# design.net
KiCad netlist of a schematic drawn in EAGLE
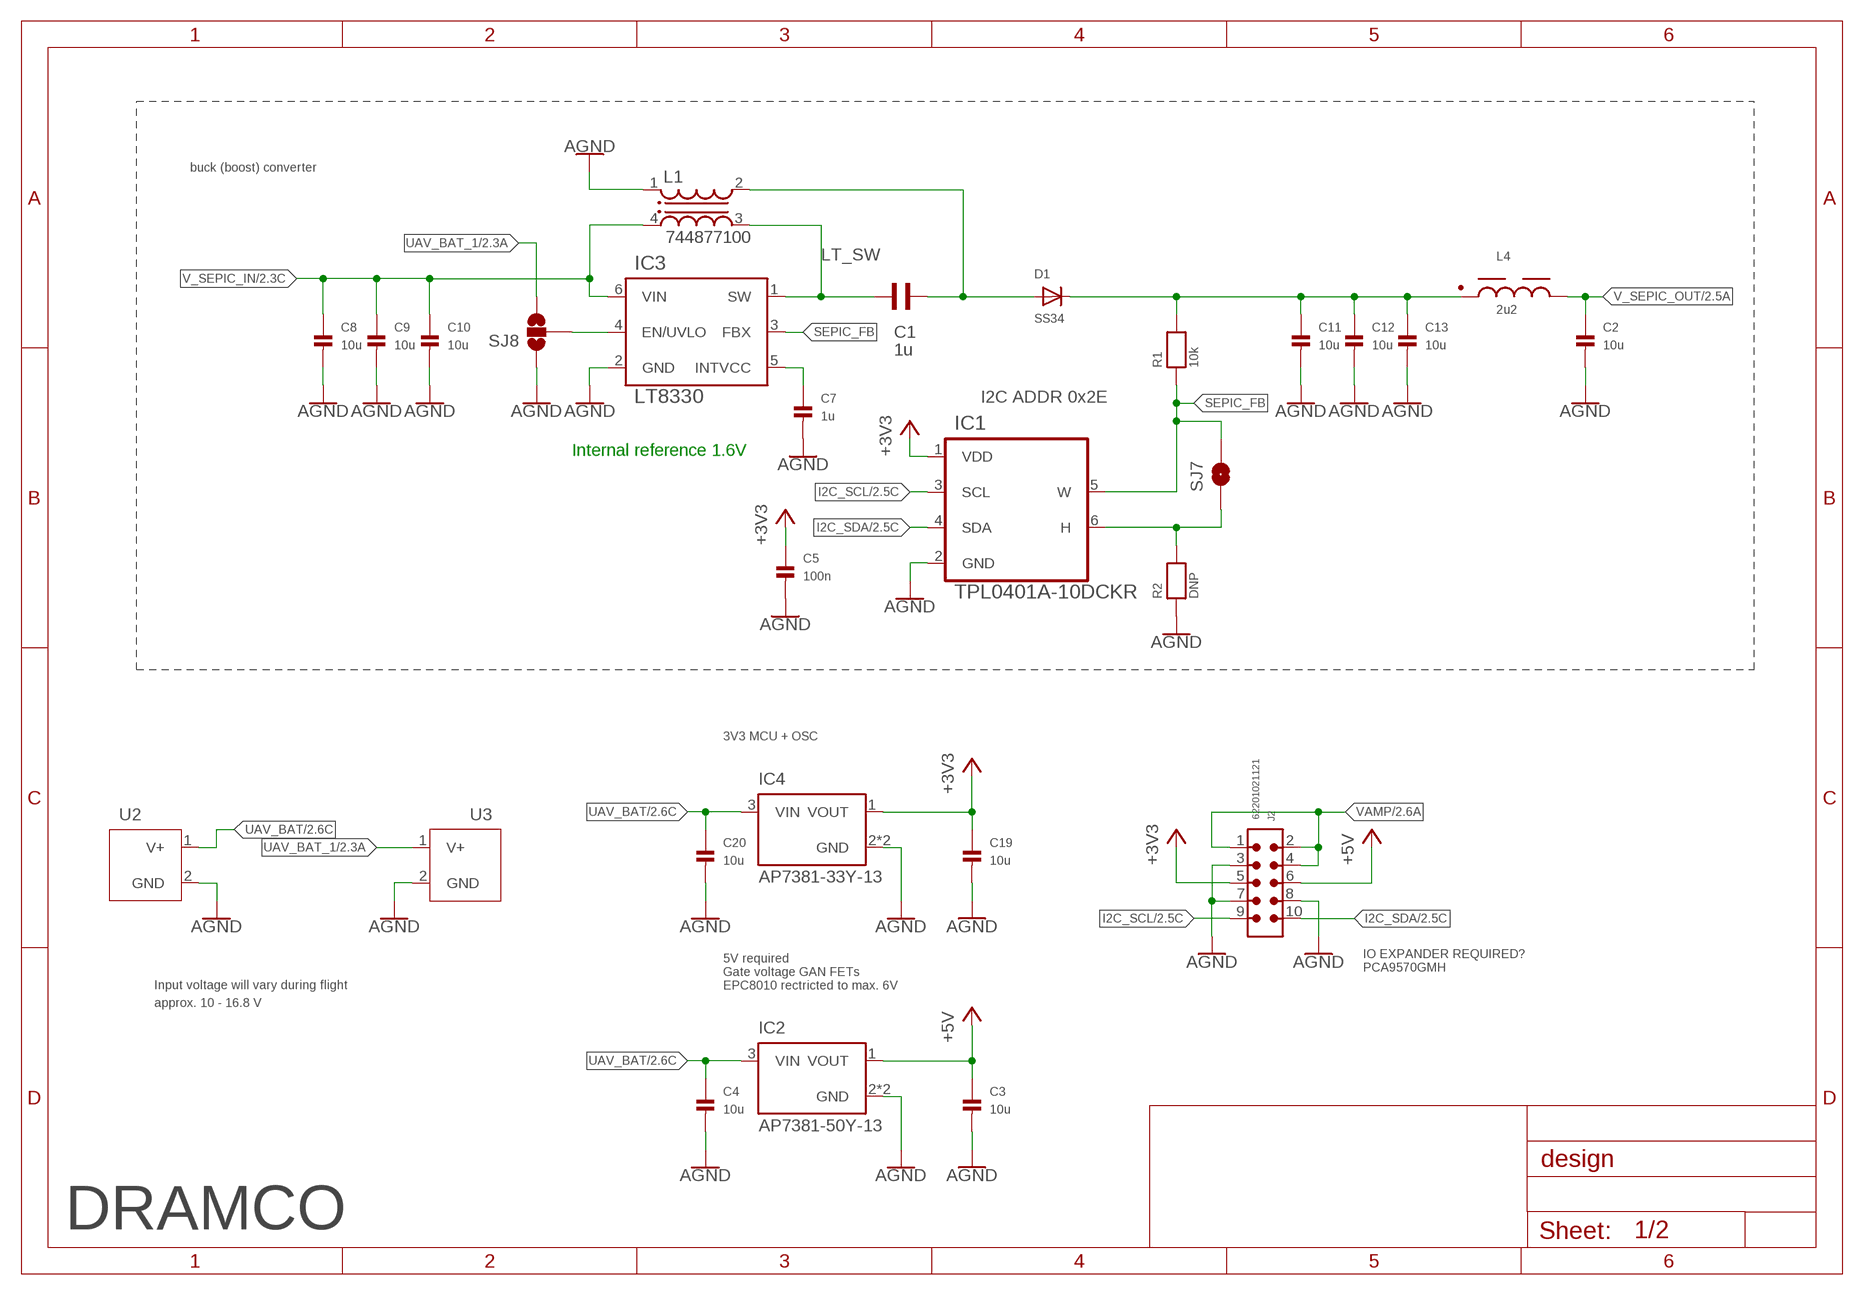
[diagram p0: schematic, sheet 1]
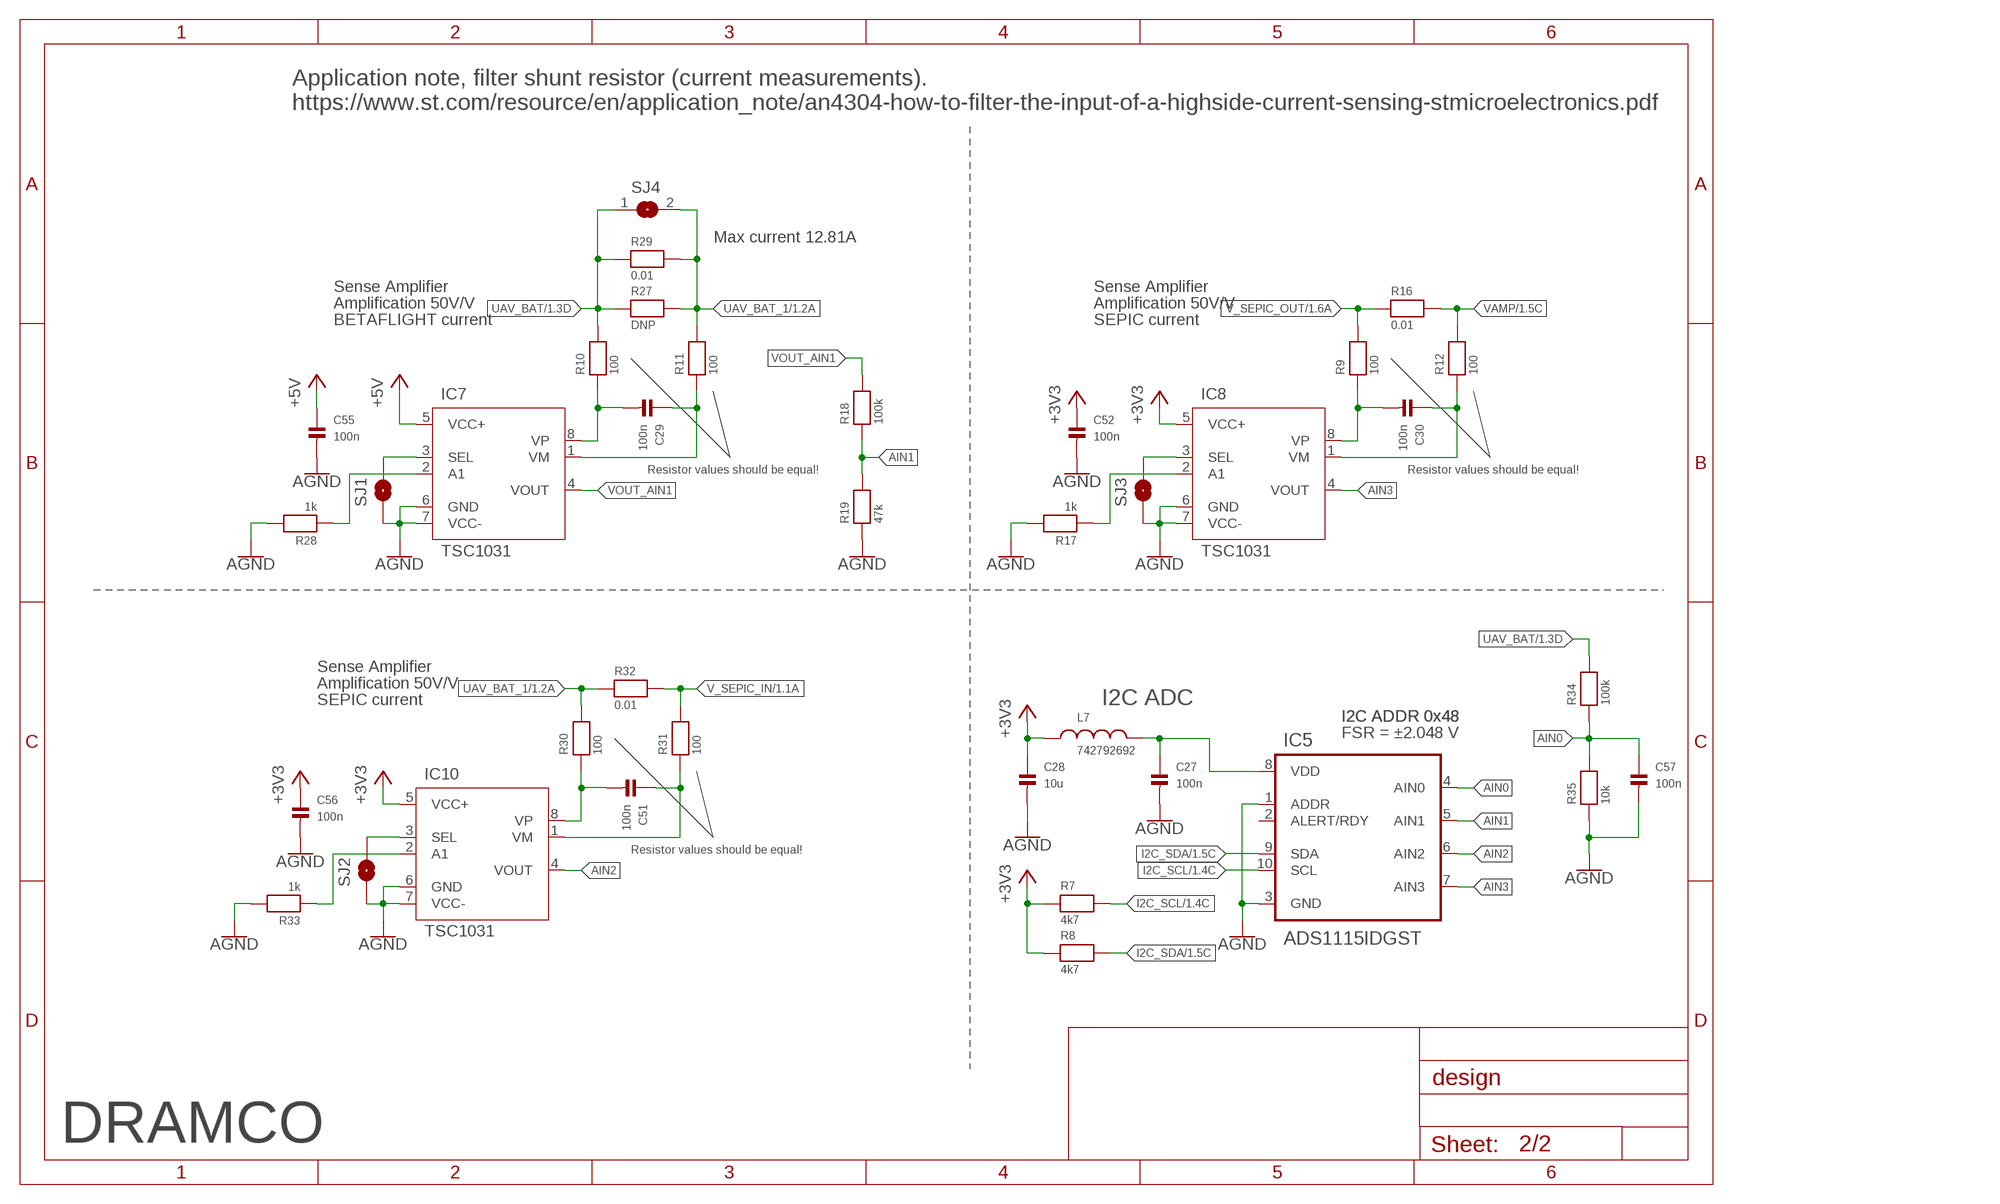
[diagram p1: schematic, sheet 2]

(export (version "E")
  (design (tool "Eeschema 10.0.6"))
  (components
    (comp (ref "C27")
      (value "100n")
      (footprint "eagle-import:0402")
      (libsource (lib "eagle-import") (part "CAP_CERAMIC0402"))
    )
    (comp (ref "C28")
      (value "10u")
      (footprint "eagle-import:0603")
      (libsource (lib "eagle-import") (part "CAP_CERAMIC0603"))
    )
    (comp (ref "C29")
      (value "100n")
      (footprint "eagle-import:0402")
      (libsource (lib "eagle-import") (part "CAP_CERAMIC0402"))
    )
    (comp (ref "C30")
      (value "100n")
      (footprint "eagle-import:0402")
      (libsource (lib "eagle-import") (part "CAP_CERAMIC0402"))
    )
    (comp (ref "C51")
      (value "100n")
      (footprint "eagle-import:0402")
      (libsource (lib "eagle-import") (part "CAP_CERAMIC0402"))
    )
    (comp (ref "C52")
      (value "100n")
      (footprint "eagle-import:0402")
      (libsource (lib "eagle-import") (part "CAP_CERAMIC0402"))
    )
    (comp (ref "C55")
      (value "100n")
      (footprint "eagle-import:0402")
      (libsource (lib "eagle-import") (part "CAP_CERAMIC0402"))
    )
    (comp (ref "C56")
      (value "100n")
      (footprint "eagle-import:0402")
      (libsource (lib "eagle-import") (part "CAP_CERAMIC0402"))
    )
    (comp (ref "C57")
      (value "100n")
      (footprint "eagle-import:0402")
      (libsource (lib "eagle-import") (part "CAP_CERAMIC0402"))
    )
    (comp (ref "IC5")
      (value "ADS1115IDGST")
      (footprint "eagle-import:SOP50P490X110-10N")
      (fields (field (name "MF") "Texas Instruments"))
      (libsource (lib "eagle-import") (part "ADS1115IDGST"))
    )
    (comp (ref "IC7")
      (value "TSC1031")
      (footprint "eagle-import:SOP65P640X120-8N")
      (libsource (lib "eagle-import") (part "TSC1031IPT"))
    )
    (comp (ref "IC8")
      (value "TSC1031")
      (footprint "eagle-import:SOP65P640X120-8N")
      (libsource (lib "eagle-import") (part "TSC1031IPT"))
    )
    (comp (ref "IC10")
      (value "TSC1031")
      (footprint "eagle-import:SOP65P640X120-8N")
      (libsource (lib "eagle-import") (part "TSC1031IPT"))
    )
    (comp (ref "L7")
      (value "742792692")
      (footprint "eagle-import:WE-CBF_0603(W=2.2)")
      (libsource (lib "eagle-import") (part "WE-CBF_0603_WB_HS_742792692"))
    )
    (comp (ref "R7")
      (value "4k7")
      (footprint "eagle-import:0603")
      (libsource (lib "eagle-import") (part "RESISTOR0603"))
    )
    (comp (ref "R8")
      (value "4k7")
      (footprint "eagle-import:0603")
      (libsource (lib "eagle-import") (part "RESISTOR0603"))
    )
    (comp (ref "R9")
      (value "100")
      (footprint "eagle-import:0402")
      (libsource (lib "eagle-import") (part "RESISTOR0402"))
    )
    (comp (ref "R10")
      (value "100")
      (footprint "eagle-import:0402")
      (libsource (lib "eagle-import") (part "RESISTOR0402"))
    )
    (comp (ref "R11")
      (value "100")
      (footprint "eagle-import:0402")
      (libsource (lib "eagle-import") (part "RESISTOR0402"))
    )
    (comp (ref "R12")
      (value "100")
      (footprint "eagle-import:0402")
      (libsource (lib "eagle-import") (part "RESISTOR0402"))
    )
    (comp (ref "R16")
      (value "0.01")
      (footprint "eagle-import:0805")
      (libsource (lib "eagle-import") (part "RESISTOR0805"))
    )
    (comp (ref "R17")
      (value "1k")
      (footprint "eagle-import:0402")
      (libsource (lib "eagle-import") (part "RESISTOR0402"))
    )
    (comp (ref "R18")
      (value "100k")
      (footprint "eagle-import:0603")
      (libsource (lib "eagle-import") (part "RESISTOR0603"))
    )
    (comp (ref "R19")
      (value "47k")
      (footprint "eagle-import:0603")
      (libsource (lib "eagle-import") (part "RESISTOR0603"))
    )
    (comp (ref "R27")
      (value "DNP")
      (footprint "eagle-import:0805")
      (libsource (lib "eagle-import") (part "RESISTOR0805"))
    )
    (comp (ref "R28")
      (value "1k")
      (footprint "eagle-import:0402")
      (libsource (lib "eagle-import") (part "RESISTOR0402"))
    )
    (comp (ref "R29")
      (value "0.01")
      (footprint "eagle-import:0805")
      (libsource (lib "eagle-import") (part "RESISTOR0805"))
    )
    (comp (ref "R30")
      (value "100")
      (footprint "eagle-import:0402")
      (libsource (lib "eagle-import") (part "RESISTOR0402"))
    )
    (comp (ref "R31")
      (value "100")
      (footprint "eagle-import:0402")
      (libsource (lib "eagle-import") (part "RESISTOR0402"))
    )
    (comp (ref "R32")
      (value "0.01")
      (footprint "eagle-import:0805")
      (libsource (lib "eagle-import") (part "RESISTOR0805"))
    )
    (comp (ref "R33")
      (value "1k")
      (footprint "eagle-import:0402")
      (libsource (lib "eagle-import") (part "RESISTOR0402"))
    )
    (comp (ref "R34")
      (value "100k")
      (footprint "eagle-import:0603")
      (libsource (lib "eagle-import") (part "RESISTOR0603"))
    )
    (comp (ref "R35")
      (value "10k")
      (footprint "eagle-import:0603")
      (libsource (lib "eagle-import") (part "RESISTOR0603"))
    )
    (comp (ref "SJ1")
      (value "SOLDERJUMPERTRACE")
      (footprint "eagle-import:SJ_2S-TRACE")
      (libsource (lib "eagle-import") (part "SOLDERJUMPERTRACE"))
    )
    (comp (ref "SJ2")
      (value "SOLDERJUMPERTRACE")
      (footprint "eagle-import:SJ_2S-TRACE")
      (libsource (lib "eagle-import") (part "SOLDERJUMPERTRACE"))
    )
    (comp (ref "SJ3")
      (value "SOLDERJUMPERTRACE")
      (footprint "eagle-import:SJ_2S-TRACE")
      (libsource (lib "eagle-import") (part "SOLDERJUMPERTRACE"))
    )
    (comp (ref "SJ4")
      (value "SOLDERJUMPERREFLOW")
      (footprint "eagle-import:SOLDERJUMPER_REFLOW")
      (libsource (lib "eagle-import") (part "SOLDERJUMPERREFLOW"))
    )
    (comp (ref "C1")
      (value "1u")
      (footprint "eagle-import:WCAP-CSGP_0805_WAVE")
      (libsource (lib "eagle-import") (part "WCAP-CSGP_0805_WAVE_885012207103"))
    )
    (comp (ref "C2")
      (value "10u")
      (footprint "eagle-import:0805")
      (libsource (lib "eagle-import") (part "CAP_CERAMIC0805"))
    )
    (comp (ref "C3")
      (value "10u")
      (footprint "eagle-import:0603")
      (libsource (lib "eagle-import") (part "CAP_CERAMIC0603"))
    )
    (comp (ref "C4")
      (value "10u")
      (footprint "eagle-import:0603")
      (libsource (lib "eagle-import") (part "CAP_CERAMIC0603"))
    )
    (comp (ref "C5")
      (value "100n")
      (footprint "eagle-import:0402")
      (libsource (lib "eagle-import") (part "CAP_CERAMIC0402"))
    )
    (comp (ref "C7")
      (value "1u")
      (footprint "eagle-import:0603")
      (libsource (lib "eagle-import") (part "CAP_CERAMIC0603"))
    )
    (comp (ref "C8")
      (value "10u")
      (footprint "eagle-import:1206")
      (libsource (lib "eagle-import") (part "CAP_CERAMIC1206"))
    )
    (comp (ref "C9")
      (value "10u")
      (footprint "eagle-import:1206")
      (libsource (lib "eagle-import") (part "CAP_CERAMIC1206"))
    )
    (comp (ref "C10")
      (value "10u")
      (footprint "eagle-import:1206")
      (libsource (lib "eagle-import") (part "CAP_CERAMIC1206"))
    )
    (comp (ref "C11")
      (value "10u")
      (footprint "eagle-import:1206")
      (libsource (lib "eagle-import") (part "CAP_CERAMIC1206"))
    )
    (comp (ref "C12")
      (value "10u")
      (footprint "eagle-import:1206")
      (libsource (lib "eagle-import") (part "CAP_CERAMIC1206"))
    )
    (comp (ref "C13")
      (value "10u")
      (footprint "eagle-import:1206")
      (libsource (lib "eagle-import") (part "CAP_CERAMIC1206"))
    )
    (comp (ref "C19")
      (value "10u")
      (footprint "eagle-import:0603")
      (libsource (lib "eagle-import") (part "CAP_CERAMIC0603"))
    )
    (comp (ref "C20")
      (value "10u")
      (footprint "eagle-import:0603")
      (libsource (lib "eagle-import") (part "CAP_CERAMIC0603"))
    )
    (comp (ref "D1")
      (value "SS34")
      (footprint "eagle-import:SOD-123")
      (libsource (lib "eagle-import") (part "DIODESOD-123"))
    )
    (comp (ref "IC1")
      (value "TPL0401A-10DCKR")
      (footprint "eagle-import:SOT65P210X110-6N")
      (fields (field (name "MF") "Texas Instruments"))
      (libsource (lib "eagle-import") (part "TPL0401A-10DCKR"))
    )
    (comp (ref "IC2")
      (value "AP7381-50Y-13")
      (footprint "eagle-import:FOOT_XC6201P332PR-G")
      (fields (field (name "MF") "Microchip") (field (name "MP") "MCP1700T-3602E/MB"))
      (libsource (lib "eagle-import") (part "AP7381-50Y-13"))
    )
    (comp (ref "IC3")
      (value "LT8330")
      (footprint "eagle-import:TSOT-23_S6")
      (fields (field (name "MF") "Analog Devices") (field (name "MP") "LT8330ES6#TR"))
      (libsource (lib "eagle-import") (part "LT8330ES6TR"))
    )
    (comp (ref "IC4")
      (value "AP7381-33Y-13")
      (footprint "eagle-import:FOOT_XC6201P332PR-G")
      (fields (field (name "MF") "Microchip") (field (name "MP") "MCP1700T-3602E/MB"))
      (libsource (lib "eagle-import") (part "AP7381-50Y-13"))
    )
    (comp (ref "J2")
      (value "62201021121")
      (footprint "eagle-import:62201021121")
      (libsource (lib "eagle-import") (part "6220XX21121_62201021121"))
    )
    (comp (ref "L1")
      (value "744877100")
      (footprint "eagle-import:WE-DD_7345")
      (libsource (lib "eagle-import") (part "WE-DD_7345_744877100"))
    )
    (comp (ref "L4")
      (value "2u2")
      (footprint "eagle-import:WE-LQS_3015")
      (libsource (lib "eagle-import") (part "WE-LQS_3015_74404032022"))
    )
    (comp (ref "R1")
      (value "10k")
      (footprint "eagle-import:0603")
      (libsource (lib "eagle-import") (part "RESISTOR0603"))
    )
    (comp (ref "R2")
      (value "DNP")
      (footprint "eagle-import:0603")
      (libsource (lib "eagle-import") (part "RESISTOR0603"))
    )
    (comp (ref "SJ7")
      (value "SOLDERJUMPERNO")
      (footprint "eagle-import:SJ_2S-NO")
      (libsource (lib "eagle-import") (part "SOLDERJUMPERNO"))
    )
    (comp (ref "SJ8")
      (value "SOLDERJUMPER_2WAYS")
      (footprint "eagle-import:SJ_3")
      (libsource (lib "eagle-import") (part "SOLDERJUMPER_2WAYS"))
    )
    (comp (ref "U2")
      (value "UAV-CONNECT")
      (footprint "eagle-import:HOLE")
      (libsource (lib "eagle-import") (part "UAV-CONNECT"))
    )
    (comp (ref "U3")
      (value "UAV-CONNECT")
      (footprint "eagle-import:HOLE")
      (libsource (lib "eagle-import") (part "UAV-CONNECT"))
    )
  )
  (nets
    (net (code "1") (name "+3V3") (class "Default")
      (node (ref "C19") (pin "1") (pinfunction "P$1_1") (pintype "passive"))
      (node (ref "C28") (pin "1") (pinfunction "P$1_1") (pintype "passive"))
      (node (ref "C5") (pin "1") (pinfunction "P$1_1") (pintype "passive"))
      (node (ref "C52") (pin "1") (pinfunction "P$1_1") (pintype "passive"))
      (node (ref "C56") (pin "1") (pinfunction "P$1_1") (pintype "passive"))
      (node (ref "IC1") (pin "1") (pinfunction "VDD_1") (pintype "power_in"))
      (node (ref "IC10") (pin "5") (pinfunction "VCC+_5") (pintype "bidirectional"))
      (node (ref "IC4") (pin "1") (pinfunction "VOUT_1") (pintype "output"))
      (node (ref "IC8") (pin "5") (pinfunction "VCC+_5") (pintype "bidirectional"))
      (node (ref "J2") (pin "5") (pinfunction "5_5") (pintype "passive"))
      (node (ref "L7") (pin "1") (pinfunction "1_1") (pintype "passive"))
      (node (ref "R7") (pin "1") (pinfunction "1_1") (pintype "passive"))
      (node (ref "R8") (pin "1") (pinfunction "1_1") (pintype "passive"))
    )
    (net (code "2") (name "+5V") (class "Default")
      (node (ref "C3") (pin "1") (pinfunction "P$1_1") (pintype "passive"))
      (node (ref "C55") (pin "1") (pinfunction "P$1_1") (pintype "passive"))
      (node (ref "IC2") (pin "1") (pinfunction "VOUT_1") (pintype "output"))
      (node (ref "IC7") (pin "5") (pinfunction "VCC+_5") (pintype "bidirectional"))
      (node (ref "J2") (pin "6") (pinfunction "6_6") (pintype "passive"))
    )
    (net (code "3") (name "AGND") (class "Default")
      (node (ref "C10") (pin "2") (pinfunction "P$2_2") (pintype "passive"))
      (node (ref "C11") (pin "2") (pinfunction "P$2_2") (pintype "passive"))
      (node (ref "C12") (pin "2") (pinfunction "P$2_2") (pintype "passive"))
      (node (ref "C13") (pin "2") (pinfunction "P$2_2") (pintype "passive"))
      (node (ref "C19") (pin "2") (pinfunction "P$2_2") (pintype "passive"))
      (node (ref "C2") (pin "2") (pinfunction "P$2_2") (pintype "passive"))
      (node (ref "C20") (pin "2") (pinfunction "P$2_2") (pintype "passive"))
      (node (ref "C27") (pin "2") (pinfunction "P$2_2") (pintype "passive"))
      (node (ref "C28") (pin "2") (pinfunction "P$2_2") (pintype "passive"))
      (node (ref "C3") (pin "2") (pinfunction "P$2_2") (pintype "passive"))
      (node (ref "C4") (pin "2") (pinfunction "P$2_2") (pintype "passive"))
      (node (ref "C5") (pin "2") (pinfunction "P$2_2") (pintype "passive"))
      (node (ref "C52") (pin "2") (pinfunction "P$2_2") (pintype "passive"))
      (node (ref "C55") (pin "2") (pinfunction "P$2_2") (pintype "passive"))
      (node (ref "C56") (pin "2") (pinfunction "P$2_2") (pintype "passive"))
      (node (ref "C57") (pin "2") (pinfunction "P$2_2") (pintype "passive"))
      (node (ref "C7") (pin "2") (pinfunction "P$2_2") (pintype "passive"))
      (node (ref "C8") (pin "2") (pinfunction "P$2_2") (pintype "passive"))
      (node (ref "C9") (pin "2") (pinfunction "P$2_2") (pintype "passive"))
      (node (ref "IC1") (pin "2") (pinfunction "GND_2") (pintype "power_in"))
      (node (ref "IC10") (pin "6") (pinfunction "GND_6") (pintype "bidirectional"))
      (node (ref "IC10") (pin "7") (pinfunction "VCC-_7") (pintype "bidirectional"))
      (node (ref "IC2") (pin "2") (pinfunction "GND_2") (pintype "power_in"))
      (node (ref "IC2") (pin "2.1") (pinfunction "GND_2.1") (pintype "power_in"))
      (node (ref "IC3") (pin "2") (pinfunction "GND_2") (pintype "power_in"))
      (node (ref "IC4") (pin "2") (pinfunction "GND_2") (pintype "power_in"))
      (node (ref "IC4") (pin "2.1") (pinfunction "GND_2.1") (pintype "power_in"))
      (node (ref "IC5") (pin "1") (pinfunction "ADDR_1") (pintype "input"))
      (node (ref "IC5") (pin "3") (pinfunction "GND_3") (pintype "passive"))
      (node (ref "IC7") (pin "6") (pinfunction "GND_6") (pintype "bidirectional"))
      (node (ref "IC7") (pin "7") (pinfunction "VCC-_7") (pintype "bidirectional"))
      (node (ref "IC8") (pin "6") (pinfunction "GND_6") (pintype "bidirectional"))
      (node (ref "IC8") (pin "7") (pinfunction "VCC-_7") (pintype "bidirectional"))
      (node (ref "J2") (pin "3") (pinfunction "3_3") (pintype "passive"))
      (node (ref "J2") (pin "7") (pinfunction "7_7") (pintype "passive"))
      (node (ref "J2") (pin "8") (pinfunction "8_8") (pintype "passive"))
      (node (ref "L1") (pin "1") (pinfunction "1_1") (pintype "passive"))
      (node (ref "R17") (pin "2") (pinfunction "2_2") (pintype "passive"))
      (node (ref "R19") (pin "1") (pinfunction "1_1") (pintype "passive"))
      (node (ref "R2") (pin "1") (pinfunction "1_1") (pintype "passive"))
      (node (ref "R28") (pin "2") (pinfunction "2_2") (pintype "passive"))
      (node (ref "R33") (pin "2") (pinfunction "2_2") (pintype "passive"))
      (node (ref "R35") (pin "1") (pinfunction "1_1") (pintype "passive"))
      (node (ref "SJ1") (pin "1") (pinfunction "1_1") (pintype "passive"))
      (node (ref "SJ2") (pin "1") (pinfunction "1_1") (pintype "passive"))
      (node (ref "SJ3") (pin "1") (pinfunction "1_1") (pintype "passive"))
      (node (ref "SJ8") (pin "1") (pinfunction "1_1") (pintype "passive"))
      (node (ref "U2") (pin "2") (pinfunction "GND_2") (pintype "bidirectional"))
      (node (ref "U3") (pin "2") (pinfunction "GND_2") (pintype "bidirectional"))
    )
    (net (code "4") (name "AIN0") (class "Default")
      (node (ref "C57") (pin "1") (pinfunction "P$1_1") (pintype "passive"))
      (node (ref "IC5") (pin "4") (pinfunction "AIN0_4") (pintype "input"))
      (node (ref "R34") (pin "1") (pinfunction "1_1") (pintype "passive"))
      (node (ref "R35") (pin "2") (pinfunction "2_2") (pintype "passive"))
    )
    (net (code "5") (name "AIN1") (class "Default")
      (node (ref "IC5") (pin "5") (pinfunction "AIN1_5") (pintype "input"))
      (node (ref "R18") (pin "1") (pinfunction "1_1") (pintype "passive"))
      (node (ref "R19") (pin "2") (pinfunction "2_2") (pintype "passive"))
    )
    (net (code "6") (name "AIN2") (class "Default")
      (node (ref "IC10") (pin "4") (pinfunction "VOUT_4") (pintype "bidirectional"))
      (node (ref "IC5") (pin "6") (pinfunction "AIN2_6") (pintype "input"))
    )
    (net (code "7") (name "AIN3") (class "Default")
      (node (ref "IC5") (pin "7") (pinfunction "AIN3_7") (pintype "input"))
      (node (ref "IC8") (pin "4") (pinfunction "VOUT_4") (pintype "bidirectional"))
    )
    (net (code "8") (name "I2C_SCL") (class "Default")
      (node (ref "IC1") (pin "3") (pinfunction "SCL_3") (pintype "bidirectional"))
      (node (ref "IC5") (pin "10") (pinfunction "SCL_10") (pintype "input"))
      (node (ref "J2") (pin "9") (pinfunction "9_9") (pintype "passive"))
      (node (ref "R7") (pin "2") (pinfunction "2_2") (pintype "passive"))
    )
    (net (code "9") (name "I2C_SDA") (class "Default")
      (node (ref "IC1") (pin "4") (pinfunction "SDA_4") (pintype "bidirectional"))
      (node (ref "IC5") (pin "9") (pinfunction "SDA_9") (pintype "bidirectional"))
      (node (ref "J2") (pin "10") (pinfunction "10_10") (pintype "passive"))
      (node (ref "R8") (pin "2") (pinfunction "2_2") (pintype "passive"))
    )
    (net (code "10") (name "LT_SW") (class "Default")
      (node (ref "C1") (pin "2") (pinfunction "2_2") (pintype "passive"))
      (node (ref "IC3") (pin "1") (pinfunction "SW_1") (pintype "output"))
      (node (ref "L1") (pin "3") (pinfunction "3_3") (pintype "passive"))
    )
    (net (code "11") (name "Net-(C1-Pad1)") (class "Default")
      (node (ref "C1") (pin "1") (pinfunction "1_1") (pintype "passive"))
      (node (ref "D1") (pin "A") (pinfunction "A_A") (pintype "passive"))
      (node (ref "L1") (pin "2") (pinfunction "2_2") (pintype "passive"))
    )
    (net (code "12") (name "Net-(C7-P$1)") (class "Default")
      (node (ref "C7") (pin "1") (pinfunction "P$1_1") (pintype "passive"))
      (node (ref "IC3") (pin "5") (pinfunction "INTVCC_5") (pintype "passive"))
    )
    (net (code "13") (name "Net-(C11-P$1)") (class "Default")
      (node (ref "C11") (pin "1") (pinfunction "P$1_1") (pintype "passive"))
      (node (ref "C12") (pin "1") (pinfunction "P$1_1") (pintype "passive"))
      (node (ref "C13") (pin "1") (pinfunction "P$1_1") (pintype "passive"))
      (node (ref "D1") (pin "C") (pinfunction "C_C") (pintype "passive"))
      (node (ref "L4") (pin "1") (pinfunction "1_1") (pintype "passive"))
      (node (ref "R1") (pin "2") (pinfunction "2_2") (pintype "passive"))
    )
    (net (code "14") (name "Net-(C27-P$1)") (class "Default")
      (node (ref "C27") (pin "1") (pinfunction "P$1_1") (pintype "passive"))
      (node (ref "IC5") (pin "8") (pinfunction "VDD_8") (pintype "power_in"))
      (node (ref "L7") (pin "2") (pinfunction "2_2") (pintype "passive"))
    )
    (net (code "15") (name "Net-(C29-P$1)") (class "Default")
      (node (ref "C29") (pin "1") (pinfunction "P$1_1") (pintype "passive"))
      (node (ref "IC7") (pin "1") (pinfunction "VM_1") (pintype "bidirectional"))
      (node (ref "R11") (pin "1") (pinfunction "1_1") (pintype "passive"))
    )
    (net (code "16") (name "Net-(C29-P$2)") (class "Default")
      (node (ref "C29") (pin "2") (pinfunction "P$2_2") (pintype "passive"))
      (node (ref "IC7") (pin "8") (pinfunction "VP_8") (pintype "bidirectional"))
      (node (ref "R10") (pin "1") (pinfunction "1_1") (pintype "passive"))
    )
    (net (code "17") (name "Net-(C30-P$1)") (class "Default")
      (node (ref "C30") (pin "1") (pinfunction "P$1_1") (pintype "passive"))
      (node (ref "IC8") (pin "1") (pinfunction "VM_1") (pintype "bidirectional"))
      (node (ref "R12") (pin "1") (pinfunction "1_1") (pintype "passive"))
    )
    (net (code "18") (name "Net-(C30-P$2)") (class "Default")
      (node (ref "C30") (pin "2") (pinfunction "P$2_2") (pintype "passive"))
      (node (ref "IC8") (pin "8") (pinfunction "VP_8") (pintype "bidirectional"))
      (node (ref "R9") (pin "1") (pinfunction "1_1") (pintype "passive"))
    )
    (net (code "19") (name "Net-(C51-P$1)") (class "Default")
      (node (ref "C51") (pin "1") (pinfunction "P$1_1") (pintype "passive"))
      (node (ref "IC10") (pin "1") (pinfunction "VM_1") (pintype "bidirectional"))
      (node (ref "R31") (pin "1") (pinfunction "1_1") (pintype "passive"))
    )
    (net (code "20") (name "Net-(C51-P$2)") (class "Default")
      (node (ref "C51") (pin "2") (pinfunction "P$2_2") (pintype "passive"))
      (node (ref "IC10") (pin "8") (pinfunction "VP_8") (pintype "bidirectional"))
      (node (ref "R30") (pin "1") (pinfunction "1_1") (pintype "passive"))
    )
    (net (code "21") (name "Net-(IC1-H)") (class "Default")
      (node (ref "IC1") (pin "6") (pinfunction "H_6") (pintype "bidirectional"))
      (node (ref "R2") (pin "2") (pinfunction "2_2") (pintype "passive"))
      (node (ref "SJ7") (pin "1") (pinfunction "1_1") (pintype "passive"))
    )
    (net (code "22") (name "Net-(IC3-EN{slash}UVLO)") (class "Default")
      (node (ref "IC3") (pin "4") (pinfunction "EN/UVLO_4") (pintype "passive"))
      (node (ref "SJ8") (pin "2") (pinfunction "2_2") (pintype "passive"))
    )
    (net (code "23") (name "Net-(IC7-A1)") (class "Default")
      (node (ref "IC7") (pin "2") (pinfunction "A1_2") (pintype "bidirectional"))
      (node (ref "R28") (pin "1") (pinfunction "1_1") (pintype "passive"))
    )
    (net (code "24") (name "Net-(IC7-SEL)") (class "Default")
      (node (ref "IC7") (pin "3") (pinfunction "SEL_3") (pintype "bidirectional"))
      (node (ref "SJ1") (pin "2") (pinfunction "2_2") (pintype "passive"))
    )
    (net (code "25") (name "Net-(IC8-A1)") (class "Default")
      (node (ref "IC8") (pin "2") (pinfunction "A1_2") (pintype "bidirectional"))
      (node (ref "R17") (pin "1") (pinfunction "1_1") (pintype "passive"))
    )
    (net (code "26") (name "Net-(IC8-SEL)") (class "Default")
      (node (ref "IC8") (pin "3") (pinfunction "SEL_3") (pintype "bidirectional"))
      (node (ref "SJ3") (pin "2") (pinfunction "2_2") (pintype "passive"))
    )
    (net (code "27") (name "Net-(IC10-A1)") (class "Default")
      (node (ref "IC10") (pin "2") (pinfunction "A1_2") (pintype "bidirectional"))
      (node (ref "R33") (pin "1") (pinfunction "1_1") (pintype "passive"))
    )
    (net (code "28") (name "Net-(IC10-SEL)") (class "Default")
      (node (ref "IC10") (pin "3") (pinfunction "SEL_3") (pintype "bidirectional"))
      (node (ref "SJ2") (pin "2") (pinfunction "2_2") (pintype "passive"))
    )
    (net (code "29") (name "SEPIC_FB") (class "Default")
      (node (ref "IC1") (pin "5") (pinfunction "W_5") (pintype "bidirectional"))
      (node (ref "IC3") (pin "3") (pinfunction "FBX_3") (pintype "output"))
      (node (ref "R1") (pin "1") (pinfunction "1_1") (pintype "passive"))
      (node (ref "SJ7") (pin "2") (pinfunction "2_2") (pintype "passive"))
    )
    (net (code "30") (name "UAV_BAT") (class "Default")
      (node (ref "C20") (pin "1") (pinfunction "P$1_1") (pintype "passive"))
      (node (ref "C4") (pin "1") (pinfunction "P$1_1") (pintype "passive"))
      (node (ref "IC2") (pin "3") (pinfunction "VIN_3") (pintype "input"))
      (node (ref "IC4") (pin "3") (pinfunction "VIN_3") (pintype "input"))
      (node (ref "R10") (pin "2") (pinfunction "2_2") (pintype "passive"))
      (node (ref "R27") (pin "1") (pinfunction "1_1") (pintype "passive"))
      (node (ref "R29") (pin "1") (pinfunction "1_1") (pintype "passive"))
      (node (ref "R34") (pin "2") (pinfunction "2_2") (pintype "passive"))
      (node (ref "SJ4") (pin "1") (pinfunction "1_1") (pintype "passive"))
      (node (ref "U2") (pin "1") (pinfunction "V+_1") (pintype "bidirectional"))
    )
    (net (code "31") (name "UAV_BAT_1") (class "Default")
      (node (ref "R11") (pin "2") (pinfunction "2_2") (pintype "passive"))
      (node (ref "R27") (pin "2") (pinfunction "2_2") (pintype "passive"))
      (node (ref "R29") (pin "2") (pinfunction "2_2") (pintype "passive"))
      (node (ref "R30") (pin "2") (pinfunction "2_2") (pintype "passive"))
      (node (ref "R32") (pin "1") (pinfunction "1_1") (pintype "passive"))
      (node (ref "SJ4") (pin "2") (pinfunction "2_2") (pintype "passive"))
      (node (ref "SJ8") (pin "3") (pinfunction "3_3") (pintype "passive"))
      (node (ref "U3") (pin "1") (pinfunction "V+_1") (pintype "bidirectional"))
    )
    (net (code "32") (name "VAMP") (class "Default")
      (node (ref "J2") (pin "1") (pinfunction "1_1") (pintype "passive"))
      (node (ref "J2") (pin "2") (pinfunction "2_2") (pintype "passive"))
      (node (ref "J2") (pin "4") (pinfunction "4_4") (pintype "passive"))
      (node (ref "R12") (pin "2") (pinfunction "2_2") (pintype "passive"))
      (node (ref "R16") (pin "2") (pinfunction "2_2") (pintype "passive"))
    )
    (net (code "33") (name "VOUT_AIN1") (class "Default")
      (node (ref "IC7") (pin "4") (pinfunction "VOUT_4") (pintype "bidirectional"))
      (node (ref "R18") (pin "2") (pinfunction "2_2") (pintype "passive"))
    )
    (net (code "34") (name "V_SEPIC_IN") (class "Default")
      (node (ref "C10") (pin "1") (pinfunction "P$1_1") (pintype "passive"))
      (node (ref "C8") (pin "1") (pinfunction "P$1_1") (pintype "passive"))
      (node (ref "C9") (pin "1") (pinfunction "P$1_1") (pintype "passive"))
      (node (ref "IC3") (pin "6") (pinfunction "VIN_6") (pintype "input"))
      (node (ref "L1") (pin "4") (pinfunction "4_4") (pintype "passive"))
      (node (ref "R31") (pin "2") (pinfunction "2_2") (pintype "passive"))
      (node (ref "R32") (pin "2") (pinfunction "2_2") (pintype "passive"))
    )
    (net (code "35") (name "V_SEPIC_OUT") (class "Default")
      (node (ref "C2") (pin "1") (pinfunction "P$1_1") (pintype "passive"))
      (node (ref "L4") (pin "2") (pinfunction "2_2") (pintype "passive"))
      (node (ref "R16") (pin "1") (pinfunction "1_1") (pintype "passive"))
      (node (ref "R9") (pin "2") (pinfunction "2_2") (pintype "passive"))
    )
    (net (code "36") (name "unconnected-(IC5-ALERT{slash}RDY-Pad2)") (class "Default")
      (node (ref "IC5") (pin "2") (pinfunction "ALERT/RDY_2") (pintype "input"))
    )
  )
)
